# bmsSlave_isospi.net
KiCad netlist of a schematic drawn in Altium Designer
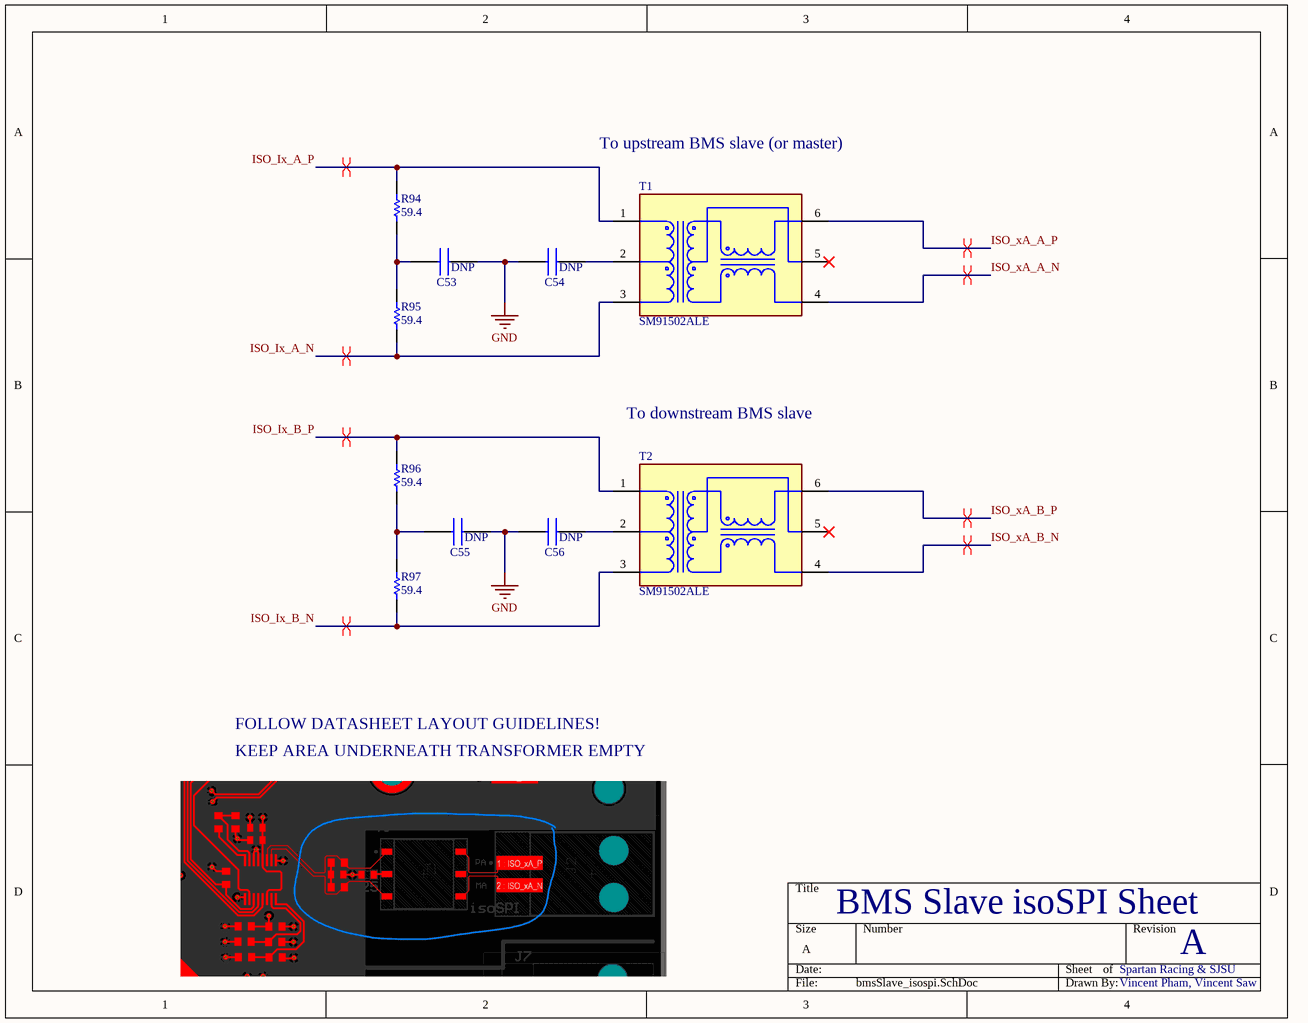
[diagram p0: bmsSlave_isospi.SchDoc]

(export (version "E")
  (design (tool "Eeschema 10.0.6"))
  (components
    (comp (ref "C53")
      (value "885382207009")
      (footprint "C0603")
      (description "Multilayer Ceramic Chip Capacitor WCAP-CSST Series 0805 10000pF X7R0805103K100DFCT1S000")
      (fields (field (name "MOUSER PART NUMBER") "710-885382207009"))
      (libsource (lib "885382207009") (part "885382207009"))
    )
    (comp (ref "C54")
      (value "885382207009")
      (footprint "C0603")
      (description "Multilayer Ceramic Chip Capacitor WCAP-CSST Series 0805 10000pF X7R0805103K100DFCT1S000")
      (fields (field (name "MOUSER PART NUMBER") "710-885382207009"))
      (libsource (lib "885382207009") (part "885382207009"))
    )
    (comp (ref "C55")
      (value "885382207009")
      (footprint "C0603")
      (description "Multilayer Ceramic Chip Capacitor WCAP-CSST Series 0805 10000pF X7R0805103K100DFCT1S000")
      (fields (field (name "MOUSER PART NUMBER") "710-885382207009"))
      (libsource (lib "885382207009") (part "885382207009"))
    )
    (comp (ref "C56")
      (value "885382207009")
      (footprint "C0603")
      (description "Multilayer Ceramic Chip Capacitor WCAP-CSST Series 0805 10000pF X7R0805103K100DFCT1S000")
      (fields (field (name "MOUSER PART NUMBER") "710-885382207009"))
      (libsource (lib "885382207009") (part "885382207009"))
    )
    (comp (ref "R94")
      (value "59.4")
      (footprint "R0603")
      (description "Resistor")
      (libsource (lib "Simulation Generic Components") (part "Resistor"))
    )
    (comp (ref "R95")
      (value "59.4")
      (footprint "R0603")
      (description "Resistor")
      (libsource (lib "Simulation Generic Components") (part "Resistor"))
    )
    (comp (ref "R96")
      (value "59.4")
      (footprint "R0603")
      (description "Resistor")
      (libsource (lib "Simulation Generic Components") (part "Resistor"))
    )
    (comp (ref "R97")
      (value "59.4")
      (footprint "R0603")
      (description "Resistor")
      (libsource (lib "Simulation Generic Components") (part "Resistor"))
    )
    (comp (ref "T1")
      (value "SM91502ALE")
      (footprint "FP-SM91502ALE-MFG")
      (description "BMS XFORMER 1-CH 1000V AECQ +125")
      (fields
        (field (name "MANUFACTURER") "Bourns")
        (field (name "OCTOPART") "https://octopart.com/sm91502ale-bourns-95732123")
      )
      (libsource (lib "Altium Content Vault") (part "554ff5199021d68917f526d8699f58a"))
    )
    (comp (ref "T2")
      (value "SM91502ALE")
      (footprint "FP-SM91502ALE-MFG")
      (description "BMS XFORMER 1-CH 1000V AECQ +125")
      (fields
        (field (name "MANUFACTURER") "Bourns")
        (field (name "OCTOPART") "https://octopart.com/sm91502ale-bourns-95732123")
      )
      (libsource (lib "Altium Content Vault") (part "554ff5199021d68917f526d8699f58a"))
    )
  )
  (nets
    (net (code "1") (name "/ISO_Ix_A_N") (class "Default")
      (node (ref "R95") (pin "2") (pinfunction "2_2") (pintype "passive"))
      (node (ref "T1") (pin "3") (pinfunction "3_3") (pintype "passive"))
    )
    (net (code "2") (name "/ISO_Ix_A_P") (class "Default")
      (node (ref "R94") (pin "1") (pinfunction "1_1") (pintype "passive"))
      (node (ref "T1") (pin "1") (pinfunction "1_1") (pintype "passive"))
    )
    (net (code "3") (name "/ISO_Ix_B_N") (class "Default")
      (node (ref "R97") (pin "2") (pinfunction "2_2") (pintype "passive"))
      (node (ref "T2") (pin "3") (pinfunction "3_3") (pintype "passive"))
    )
    (net (code "4") (name "/ISO_Ix_B_P") (class "Default")
      (node (ref "R96") (pin "1") (pinfunction "1_1") (pintype "passive"))
      (node (ref "T2") (pin "1") (pinfunction "1_1") (pintype "passive"))
    )
    (net (code "5") (name "/ISO_xA_A_N") (class "Default")
      (node (ref "T1") (pin "4") (pinfunction "4_4") (pintype "passive"))
    )
    (net (code "6") (name "/ISO_xA_A_P") (class "Default")
      (node (ref "T1") (pin "6") (pinfunction "6_6") (pintype "passive"))
    )
    (net (code "7") (name "/ISO_xA_B_N") (class "Default")
      (node (ref "T2") (pin "4") (pinfunction "4_4") (pintype "passive"))
    )
    (net (code "8") (name "/ISO_xA_B_P") (class "Default")
      (node (ref "T2") (pin "6") (pinfunction "6_6") (pintype "passive"))
    )
    (net (code "9") (name "GND") (class "Default")
      (node (ref "C53") (pin "1") (pinfunction "1_1") (pintype "passive"))
      (node (ref "C54") (pin "2") (pinfunction "2_2") (pintype "passive"))
      (node (ref "C55") (pin "1") (pinfunction "1_1") (pintype "passive"))
      (node (ref "C56") (pin "2") (pinfunction "2_2") (pintype "passive"))
    )
    (net (code "10") (name "Net-(C53-Pad2)") (class "Default")
      (node (ref "C53") (pin "2") (pinfunction "2_2") (pintype "passive"))
      (node (ref "R94") (pin "2") (pinfunction "2_2") (pintype "passive"))
      (node (ref "R95") (pin "1") (pinfunction "1_1") (pintype "passive"))
    )
    (net (code "11") (name "Net-(C54-Pad1)") (class "Default")
      (node (ref "C54") (pin "1") (pinfunction "1_1") (pintype "passive"))
      (node (ref "T1") (pin "2") (pinfunction "2_2") (pintype "passive"))
    )
    (net (code "12") (name "Net-(C55-Pad2)") (class "Default")
      (node (ref "C55") (pin "2") (pinfunction "2_2") (pintype "passive"))
      (node (ref "R96") (pin "2") (pinfunction "2_2") (pintype "passive"))
      (node (ref "R97") (pin "1") (pinfunction "1_1") (pintype "passive"))
    )
    (net (code "13") (name "Net-(C56-Pad1)") (class "Default")
      (node (ref "C56") (pin "1") (pinfunction "1_1") (pintype "passive"))
      (node (ref "T2") (pin "2") (pinfunction "2_2") (pintype "passive"))
    )
    (net (code "14") (name "unconnected-(T1-Pad5)") (class "Default")
      (node (ref "T1") (pin "5") (pinfunction "5_5") (pintype "passive+no_connect"))
    )
    (net (code "15") (name "unconnected-(T2-Pad5)") (class "Default")
      (node (ref "T2") (pin "5") (pinfunction "5_5") (pintype "passive+no_connect"))
    )
  )
)
